# Cyusb3014_-_2.net
KiCad netlist of a schematic drawn in Altium Designer
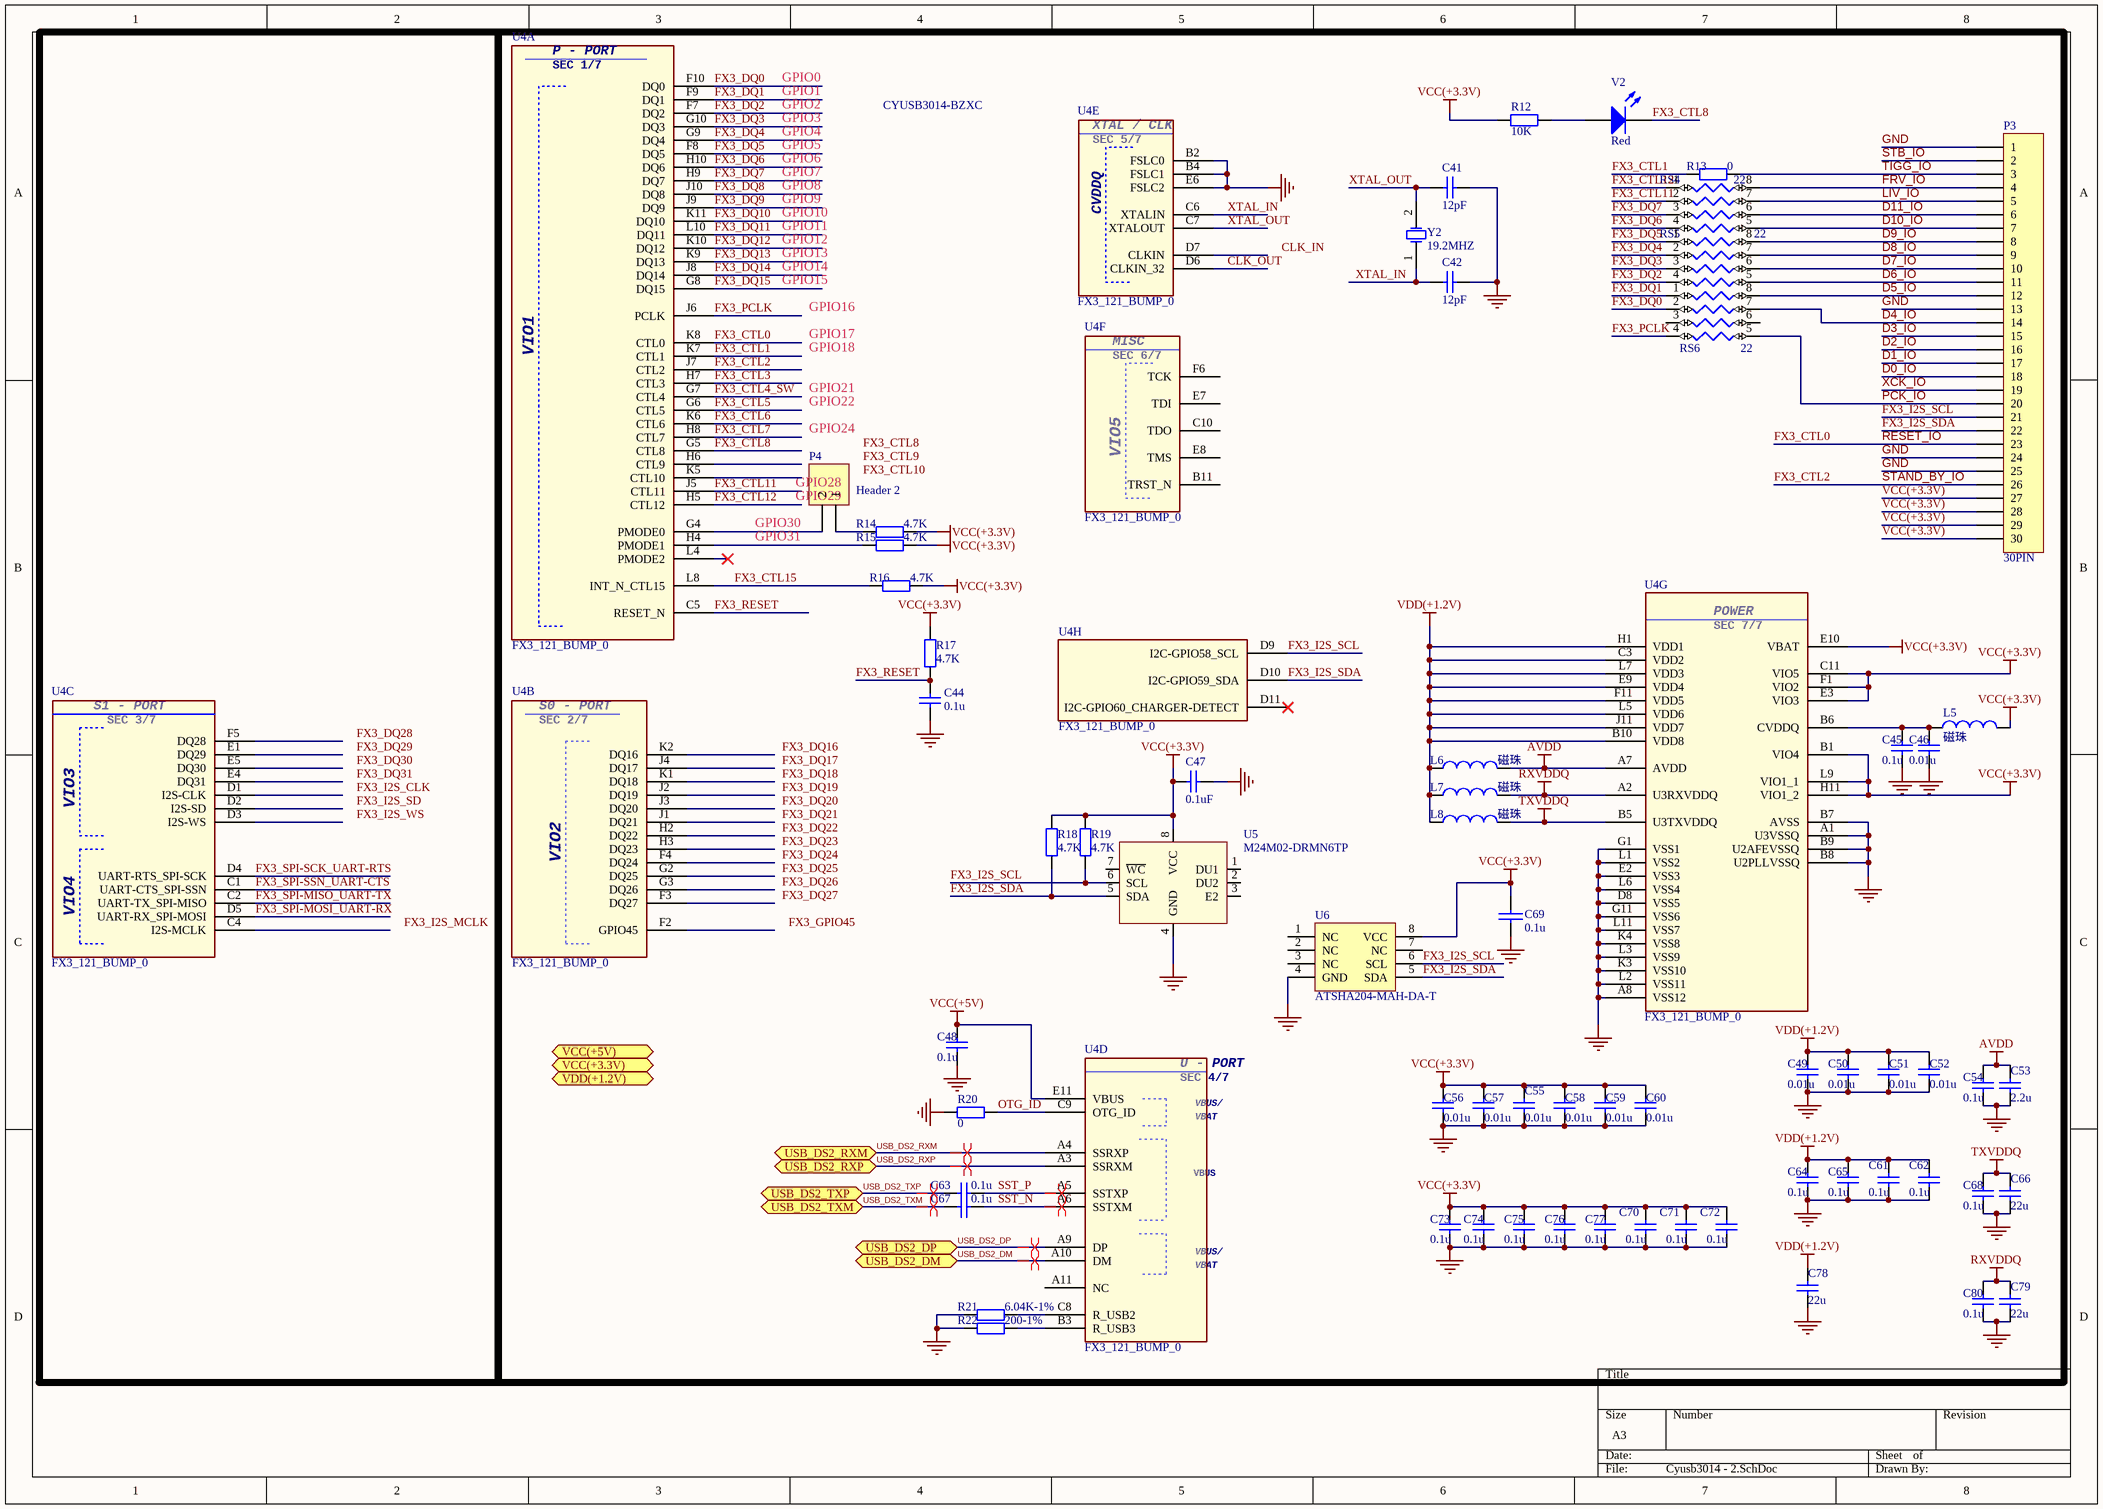
[diagram p0: Cyusb3014 - 2.SchDoc]

(export (version "E")
  (design (tool "Eeschema 10.0.6"))
  (components
    (comp (ref "C41")
      (value "12pF")
      (footprint "0603S-CAP")
      (description "CAP CER SMT 4.3pF 0805")
      (fields
        (field (name "2. MANUFACTURERE PART NUMBER") "C0805C439D5GACTU")
        (field (name "8. ALTERNATE PART") "any")
      )
      (libsource (lib "Peeple_eval") (part "CAP CER SMT 4.3pF 0805"))
    )
    (comp (ref "C42")
      (value "12pF")
      (footprint "0603S-CAP")
      (description "CAP CER SMT 4.3pF 0805")
      (fields
        (field (name "2. MANUFACTURERE PART NUMBER") "C0805C439D5GACTU")
        (field (name "8. ALTERNATE PART") "any")
      )
      (libsource (lib "Peeple_eval") (part "CAP CER SMT 4.3pF 0805"))
    )
    (comp (ref "C44")
      (value "0.1u")
      (footprint "0603S-CAP")
      (description "50V/8.2u/0805")
      (fields (field (name "PUBLISHER") "Altium Limited"))
      (libsource (lib "Miscellaneous Devices") (part "Cap"))
    )
    (comp (ref "C45")
      (value "0.1u")
      (footprint "C0402")
      (description "Capacitor")
      (fields (field (name "PUBLISHER") "Altium Limited"))
      (libsource (lib "WM360") (part "CAP0805"))
    )
    (comp (ref "C46")
      (value "0.01u")
      (footprint "C0402")
      (description "Capacitor")
      (fields (field (name "PUBLISHER") "Altium Limited"))
      (libsource (lib "WM360") (part "CAP0805"))
    )
    (comp (ref "C47")
      (value "0.1uF")
      (footprint "0603S-CAP")
      (description "CAP SMT 0.1uF 16V X7R")
      (fields
        (field (name "2. MANUFACTURERE PART NUMBER") "C0805C104K4RACTU")
        (field (name "8. ALTERNATE PART") "any")
      )
      (libsource (lib "Peeple_eval") (part "CAP SMT 0.1uF 16V X7R"))
    )
    (comp (ref "C48")
      (value "0.1u")
      (footprint "C0402")
      (description "Capacitor")
      (fields (field (name "PUBLISHER") "Altium Limited"))
      (libsource (lib "WM360") (part "CAP0805"))
    )
    (comp (ref "C49")
      (value "0.01u")
      (footprint "C0402")
      (description "Capacitor")
      (fields (field (name "PUBLISHER") "Altium Limited"))
      (libsource (lib "WM360") (part "CAP0805"))
    )
    (comp (ref "C50")
      (value "0.01u")
      (footprint "C0402")
      (description "Capacitor")
      (fields (field (name "PUBLISHER") "Altium Limited"))
      (libsource (lib "WM360") (part "CAP0805"))
    )
    (comp (ref "C51")
      (value "0.01u")
      (footprint "C0402")
      (description "Capacitor")
      (fields (field (name "PUBLISHER") "Altium Limited"))
      (libsource (lib "WM360") (part "CAP0805"))
    )
    (comp (ref "C52")
      (value "0.01u")
      (footprint "C0402")
      (description "Capacitor")
      (fields (field (name "PUBLISHER") "Altium Limited"))
      (libsource (lib "WM360") (part "CAP0805"))
    )
    (comp (ref "C53")
      (value "2.2u")
      (footprint "C0805S-CAP")
      (description "Capacitor")
      (fields (field (name "PUBLISHER") "Altium Limited"))
      (libsource (lib "USB_CAMERA") (part "CAP0805"))
    )
    (comp (ref "C54")
      (value "0.1u")
      (footprint "C0402")
      (description "Capacitor")
      (fields (field (name "PUBLISHER") "Altium Limited"))
      (libsource (lib "WM360") (part "CAP0805"))
    )
    (comp (ref "C55")
      (value "0.01u")
      (footprint "C0402")
      (description "Capacitor")
      (fields (field (name "PUBLISHER") "Altium Limited"))
      (libsource (lib "WM360") (part "CAP0805"))
    )
    (comp (ref "C56")
      (value "0.01u")
      (footprint "C0402")
      (description "Capacitor")
      (fields (field (name "PUBLISHER") "Altium Limited"))
      (libsource (lib "WM360") (part "CAP0805"))
    )
    (comp (ref "C57")
      (value "0.01u")
      (footprint "C0402")
      (description "Capacitor")
      (fields (field (name "PUBLISHER") "Altium Limited"))
      (libsource (lib "WM360") (part "CAP0805"))
    )
    (comp (ref "C58")
      (value "0.01u")
      (footprint "C0402")
      (description "Capacitor")
      (fields (field (name "PUBLISHER") "Altium Limited"))
      (libsource (lib "WM360") (part "CAP0805"))
    )
    (comp (ref "C59")
      (value "0.01u")
      (footprint "C0402")
      (description "Capacitor")
      (fields (field (name "PUBLISHER") "Altium Limited"))
      (libsource (lib "WM360") (part "CAP0805"))
    )
    (comp (ref "C60")
      (value "0.01u")
      (footprint "C0402")
      (description "Capacitor")
      (fields (field (name "PUBLISHER") "Altium Limited"))
      (libsource (lib "WM360") (part "CAP0805"))
    )
    (comp (ref "C61")
      (value "0.1u")
      (footprint "C0402")
      (description "Capacitor")
      (fields (field (name "PUBLISHER") "Altium Limited"))
      (libsource (lib "WM360") (part "CAP0805"))
    )
    (comp (ref "C62")
      (value "0.1u")
      (footprint "C0402")
      (description "Capacitor")
      (fields (field (name "PUBLISHER") "Altium Limited"))
      (libsource (lib "WM360") (part "CAP0805"))
    )
    (comp (ref "C63")
      (value "0.1u")
      (footprint "C0402")
      (description "Capacitor")
      (fields (field (name "PUBLISHER") "Altium Limited"))
      (libsource (lib "WM360") (part "CAP0805"))
    )
    (comp (ref "C64")
      (value "0.1u")
      (footprint "C0402")
      (description "Capacitor")
      (fields (field (name "PUBLISHER") "Altium Limited"))
      (libsource (lib "WM360") (part "CAP0805"))
    )
    (comp (ref "C65")
      (value "0.1u")
      (footprint "C0402")
      (description "Capacitor")
      (fields (field (name "PUBLISHER") "Altium Limited"))
      (libsource (lib "WM360") (part "CAP0805"))
    )
    (comp (ref "C66")
      (value "22u")
      (footprint "C0805S-CAP")
      (description "Capacitor")
      (fields (field (name "PUBLISHER") "Altium Limited"))
      (libsource (lib "USB_CAMERA") (part "CAP0805"))
    )
    (comp (ref "C67")
      (value "0.1u")
      (footprint "C0402")
      (description "Capacitor")
      (fields (field (name "PUBLISHER") "Altium Limited"))
      (libsource (lib "WM360") (part "CAP0805"))
    )
    (comp (ref "C68")
      (value "0.1u")
      (footprint "C0402")
      (description "Capacitor")
      (fields (field (name "PUBLISHER") "Altium Limited"))
      (libsource (lib "WM360") (part "CAP0805"))
    )
    (comp (ref "C69")
      (value "0.1u")
      (footprint "0603S-CAP")
      (description "RC=1206")
      (libsource (lib "*") (part "CAP"))
    )
    (comp (ref "C70")
      (value "0.1u")
      (footprint "C0402")
      (description "Capacitor")
      (fields (field (name "PUBLISHER") "Altium Limited"))
      (libsource (lib "WM360") (part "CAP0805"))
    )
    (comp (ref "C71")
      (value "0.1u")
      (footprint "C0402")
      (description "Capacitor")
      (fields (field (name "PUBLISHER") "Altium Limited"))
      (libsource (lib "WM360") (part "CAP0805"))
    )
    (comp (ref "C72")
      (value "0.1u")
      (footprint "C0402")
      (description "Capacitor")
      (fields (field (name "PUBLISHER") "Altium Limited"))
      (libsource (lib "WM360") (part "CAP0805"))
    )
    (comp (ref "C73")
      (value "0.1u")
      (footprint "C0402")
      (description "Capacitor")
      (fields (field (name "PUBLISHER") "Altium Limited"))
      (libsource (lib "WM360") (part "CAP0805"))
    )
    (comp (ref "C74")
      (value "0.1u")
      (footprint "C0402")
      (description "Capacitor")
      (fields (field (name "PUBLISHER") "Altium Limited"))
      (libsource (lib "WM360") (part "CAP0805"))
    )
    (comp (ref "C75")
      (value "0.1u")
      (footprint "C0402")
      (description "Capacitor")
      (fields (field (name "PUBLISHER") "Altium Limited"))
      (libsource (lib "WM360") (part "CAP0805"))
    )
    (comp (ref "C76")
      (value "0.1u")
      (footprint "C0402")
      (description "Capacitor")
      (fields (field (name "PUBLISHER") "Altium Limited"))
      (libsource (lib "WM360") (part "CAP0805"))
    )
    (comp (ref "C77")
      (value "0.1u")
      (footprint "C0402")
      (description "Capacitor")
      (fields (field (name "PUBLISHER") "Altium Limited"))
      (libsource (lib "WM360") (part "CAP0805"))
    )
    (comp (ref "C78")
      (value "22u")
      (footprint "C0805S-CAP")
      (description "Capacitor")
      (fields (field (name "PUBLISHER") "Altium Limited"))
      (libsource (lib "USB_CAMERA") (part "CAP0805"))
    )
    (comp (ref "C79")
      (value "22u")
      (footprint "C0805S-CAP")
      (description "Capacitor")
      (fields (field (name "PUBLISHER") "Altium Limited"))
      (libsource (lib "USB_CAMERA") (part "CAP0805"))
    )
    (comp (ref "C80")
      (value "0.1u")
      (footprint "C0402")
      (description "Capacitor")
      (fields (field (name "PUBLISHER") "Altium Limited"))
      (libsource (lib "WM360") (part "CAP0805"))
    )
    (comp (ref "L5")
      (value "磁珠")
      (footprint "L0603")
      (description "Inductor")
      (fields (field (name "PUBLISHER") "Altium Limited"))
      (libsource (lib "Miscellaneous Devices") (part "Inductor"))
    )
    (comp (ref "L6")
      (value "磁珠")
      (footprint "L0603")
      (description "Inductor")
      (fields (field (name "PUBLISHER") "Altium Limited"))
      (libsource (lib "Miscellaneous Devices") (part "Inductor"))
    )
    (comp (ref "L7")
      (value "磁珠")
      (footprint "L0603")
      (description "Inductor")
      (fields (field (name "PUBLISHER") "Altium Limited"))
      (libsource (lib "Miscellaneous Devices") (part "Inductor"))
    )
    (comp (ref "L8")
      (value "磁珠")
      (footprint "L0603")
      (description "Inductor")
      (fields (field (name "PUBLISHER") "Altium Limited"))
      (libsource (lib "Miscellaneous Devices") (part "Inductor"))
    )
    (comp (ref "P3")
      (value "30PIN")
      (footprint "FH12-30S-0.5SH")
      (description "Header, 30-Pin")
      (fields (field (name "PUBLISHER") "Altium Limited"))
      (libsource (lib "Miscellaneous Connectors") (part "Header 30"))
    )
    (comp (ref "P4")
      (value "Header 2")
      (footprint "HDR1X2")
      (description "Header, 2-Pin")
      (fields (field (name "PUBLISHER") "Altium Limited"))
      (libsource (lib "Miscellaneous Connectors") (part "Header 2"))
    )
    (comp (ref "R12")
      (value "10K")
      (footprint "0603S-RES")
      (description "Resistor")
      (fields (field (name "PUBLISHER") "Altium Limited"))
      (libsource (lib "DM642") (part "Res2"))
    )
    (comp (ref "R13")
      (value "0")
      (footprint "0603S-RES")
      (description "Resistor")
      (fields (field (name "PUBLISHER") "Altium Limited"))
      (libsource (lib "DM642") (part "Res2"))
    )
    (comp (ref "R14")
      (value "4.7K")
      (footprint "0603S-RES")
      (description "Resistor")
      (fields (field (name "PUBLISHER") "Altium Limited"))
      (libsource (lib "") (part "Res2_3"))
    )
    (comp (ref "R15")
      (value "4.7K")
      (footprint "0603S-RES")
      (description "Resistor")
      (fields (field (name "PUBLISHER") "Altium Limited"))
      (libsource (lib "") (part "Res2_3"))
    )
    (comp (ref "R16")
      (value "4.7K")
      (footprint "0603S-RES")
      (description "Resistor")
      (fields (field (name "PUBLISHER") "Altium Limited"))
      (libsource (lib "") (part "Res2_1"))
    )
    (comp (ref "R17")
      (value "4.7K")
      (footprint "0603S-RES")
      (description "Resistor")
      (fields (field (name "PUBLISHER") "Altium Limited"))
      (libsource (lib "") (part "Res2_2"))
    )
    (comp (ref "R18")
      (value "4.7K")
      (footprint "0603S-RES")
      (description "Resistor")
      (fields (field (name "PUBLISHER") "Altium Limited"))
      (libsource (lib "") (part "Res2_3"))
    )
    (comp (ref "R19")
      (value "4.7K")
      (footprint "0603S-RES")
      (description "Resistor")
      (fields (field (name "PUBLISHER") "Altium Limited"))
      (libsource (lib "") (part "Res2_3"))
    )
    (comp (ref "R20")
      (value "0")
      (footprint "0603S-RES")
      (description "Resistor")
      (fields (field (name "PUBLISHER") "Altium Limited"))
      (libsource (lib "") (part "Res2_1"))
    )
    (comp (ref "R21")
      (value "6.04K-1%")
      (footprint "0603S-RES")
      (description "Resistor")
      (fields (field (name "PUBLISHER") "Altium Limited"))
      (libsource (lib "") (part "Res2_1"))
    )
    (comp (ref "R22")
      (value "200-1%")
      (footprint "0603S-RES")
      (description "Resistor")
      (fields (field (name "PUBLISHER") "Altium Limited"))
      (libsource (lib "") (part "Res2_1"))
    )
    (comp (ref "RS4") (value "22") (footprint "NC06-4") (libsource (lib "*") (part "RN4")))
    (comp (ref "RS5") (value "22") (footprint "NC06-4") (libsource (lib "*") (part "RN4")))
    (comp (ref "RS6") (value "22") (footprint "NC06-4") (libsource (lib "*") (part "RN4")))
    (comp (ref "U4")
      (value "FX3_121_BUMP_0")
      (footprint "121_BGA_FX3")
      (libsource (lib "") (part "FX3_121_BUMP_0_1"))
    )
    (comp (ref "U5")
      (value "M24M02-DRMN6TP")
      (footprint "SOIC127P600X175-8N")
      (description "IC EEPROM 64KBIT 400KHZ 8SOIC")
      (fields
        (field (name "MANUFACTURER") "Microchip Technology")
        (field (name "MANUFACTURER PART NUMBER") "24LC64-I/SN")
      )
      (libsource (lib "Schlib1") (part "24LC64-I/SN"))
    )
    (comp (ref "U6")
      (value "ATSHA204-MAH-DA-T")
      (footprint "UDFN")
      (libsource (lib "CY7C68013-56") (part "AT24C128"))
    )
    (comp (ref "V2")
      (value "Red")
      (footprint "LED0805S")
      (description "Typical INFRARED GaAs LED")
      (fields (field (name "PUBLISHER") "Altium Limited"))
      (libsource (lib "DM642") (part "LED0"))
    )
    (comp (ref "Y2")
      (value "19.2MHZ")
      (footprint "爱普生晶振3.2×2.5MM - 无源")
      (description "Crystal, CRYSTAL 32.768KHZ 6PF SMD")
      (fields
        (field (name "2. MANUFACTURERE PART NUMBER") "ABS07-120-32.768KHZ-T")
        (field (name "4. SUPPLIER PART NUMBER") "535-11937-1-ND")
      )
      (libsource (lib "Peeple_eval") (part "XTAL 32.768KHZ"))
    )
  )
  (nets
    (net (code "2") (name "/CLK_OUT") (class "Default")
      (node (ref "U4") (pin "D6") (pinfunction "CLKIN_32_D6") (pintype "passive"))
    )
    (net (code "3") (name "/D0_IO") (class "Default")
      (node (ref "P3") (pin "18") (pinfunction "18_18") (pintype "passive"))
    )
    (net (code "4") (name "/D1_IO") (class "Default")
      (node (ref "P3") (pin "17") (pinfunction "17_17") (pintype "passive"))
    )
    (net (code "5") (name "/D2_IO") (class "Default")
      (node (ref "P3") (pin "16") (pinfunction "16_16") (pintype "passive"))
    )
    (net (code "6") (name "/D3_IO") (class "Default")
      (node (ref "P3") (pin "15") (pinfunction "15_15") (pintype "passive"))
    )
    (net (code "7") (name "/D4_IO") (class "Default")
      (node (ref "P3") (pin "14") (pinfunction "14_14") (pintype "passive"))
      (node (ref "RS6") (pin "7") (pinfunction "7_7") (pintype "bidirectional"))
    )
    (net (code "8") (name "/D5_IO") (class "Default")
      (node (ref "P3") (pin "12") (pinfunction "12_12") (pintype "passive"))
      (node (ref "RS6") (pin "8") (pinfunction "8_8") (pintype "bidirectional"))
    )
    (net (code "9") (name "/D6_IO") (class "Default")
      (node (ref "P3") (pin "11") (pinfunction "11_11") (pintype "passive"))
      (node (ref "RS5") (pin "5") (pinfunction "5_5") (pintype "bidirectional"))
    )
    (net (code "10") (name "/D7_IO") (class "Default")
      (node (ref "P3") (pin "10") (pinfunction "10_10") (pintype "passive"))
      (node (ref "RS5") (pin "6") (pinfunction "6_6") (pintype "bidirectional"))
    )
    (net (code "11") (name "/D8_IO") (class "Default")
      (node (ref "P3") (pin "9") (pinfunction "9_9") (pintype "passive"))
      (node (ref "RS5") (pin "7") (pinfunction "7_7") (pintype "bidirectional"))
    )
    (net (code "12") (name "/D9_IO") (class "Default")
      (node (ref "P3") (pin "8") (pinfunction "8_8") (pintype "passive"))
      (node (ref "RS5") (pin "8") (pinfunction "8_8") (pintype "bidirectional"))
    )
    (net (code "13") (name "/D10_IO") (class "Default")
      (node (ref "P3") (pin "7") (pinfunction "7_7") (pintype "passive"))
      (node (ref "RS4") (pin "5") (pinfunction "5_5") (pintype "bidirectional"))
    )
    (net (code "14") (name "/D11_IO") (class "Default")
      (node (ref "P3") (pin "6") (pinfunction "6_6") (pintype "passive"))
      (node (ref "RS4") (pin "6") (pinfunction "6_6") (pintype "bidirectional"))
    )
    (net (code "15") (name "/FRV_IO") (class "Default")
      (node (ref "P3") (pin "4") (pinfunction "4_4") (pintype "passive"))
      (node (ref "RS4") (pin "8") (pinfunction "8_8") (pintype "bidirectional"))
    )
    (net (code "16") (name "/FX3_CTL0") (class "Default")
      (node (ref "P3") (pin "23") (pinfunction "23_23") (pintype "passive"))
      (node (ref "U4") (pin "K8") (pinfunction "CTL0_K8") (pintype "passive"))
    )
    (net (code "17") (name "/FX3_CTL1") (class "Default")
      (node (ref "R13") (pin "2") (pinfunction "2_2") (pintype "passive"))
      (node (ref "U4") (pin "K7") (pinfunction "CTL1_K7") (pintype "passive"))
    )
    (net (code "18") (name "/FX3_CTL2") (class "Default")
      (node (ref "P3") (pin "26") (pinfunction "26_26") (pintype "passive"))
      (node (ref "U4") (pin "J7") (pinfunction "CTL2_J7") (pintype "passive"))
    )
    (net (code "19") (name "/FX3_CTL3") (class "Default")
      (node (ref "U4") (pin "H7") (pinfunction "CTL3_H7") (pintype "passive"))
    )
    (net (code "20") (name "/FX3_CTL4_SW") (class "Default")
      (node (ref "U4") (pin "G7") (pinfunction "CTL4_G7") (pintype "passive"))
    )
    (net (code "21") (name "/FX3_CTL5") (class "Default")
      (node (ref "U4") (pin "G6") (pinfunction "CTL5_G6") (pintype "passive"))
    )
    (net (code "22") (name "/FX3_CTL6") (class "Default")
      (node (ref "U4") (pin "K6") (pinfunction "CTL6_K6") (pintype "passive"))
    )
    (net (code "23") (name "/FX3_CTL7") (class "Default")
      (node (ref "U4") (pin "H8") (pinfunction "CTL7_H8") (pintype "passive"))
    )
    (net (code "24") (name "/FX3_CTL8") (class "Default")
      (node (ref "U4") (pin "G5") (pinfunction "CTL8_G5") (pintype "passive"))
      (node (ref "V2") (pin "2") (pinfunction "K_2") (pintype "passive"))
    )
    (net (code "27") (name "/FX3_CTL11") (class "Default")
      (node (ref "RS4") (pin "2") (pinfunction "2_2") (pintype "bidirectional"))
      (node (ref "U4") (pin "J5") (pinfunction "CTL11_J5") (pintype "passive"))
    )
    (net (code "28") (name "/FX3_CTL12") (class "Default")
      (node (ref "RS4") (pin "1") (pinfunction "1_1") (pintype "bidirectional"))
      (node (ref "U4") (pin "H5") (pinfunction "CTL12_H5") (pintype "passive"))
    )
    (net (code "29") (name "/FX3_CTL15") (class "Default")
      (node (ref "R16") (pin "2") (pinfunction "2_2") (pintype "passive"))
      (node (ref "U4") (pin "L8") (pinfunction "INT_N_CTL15_L8") (pintype "passive"))
    )
    (net (code "30") (name "/FX3_DQ0") (class "Default")
      (node (ref "RS6") (pin "2") (pinfunction "2_2") (pintype "bidirectional"))
      (node (ref "U4") (pin "F10") (pinfunction "DQ0_F10") (pintype "passive"))
    )
    (net (code "31") (name "/FX3_DQ1") (class "Default")
      (node (ref "RS6") (pin "1") (pinfunction "1_1") (pintype "bidirectional"))
      (node (ref "U4") (pin "F9") (pinfunction "DQ1_F9") (pintype "passive"))
    )
    (net (code "32") (name "/FX3_DQ2") (class "Default")
      (node (ref "RS5") (pin "4") (pinfunction "4_4") (pintype "bidirectional"))
      (node (ref "U4") (pin "F7") (pinfunction "DQ2_F7") (pintype "passive"))
    )
    (net (code "33") (name "/FX3_DQ3") (class "Default")
      (node (ref "RS5") (pin "3") (pinfunction "3_3") (pintype "bidirectional"))
      (node (ref "U4") (pin "G10") (pinfunction "DQ3_G10") (pintype "passive"))
    )
    (net (code "34") (name "/FX3_DQ4") (class "Default")
      (node (ref "RS5") (pin "2") (pinfunction "2_2") (pintype "bidirectional"))
      (node (ref "U4") (pin "G9") (pinfunction "DQ4_G9") (pintype "passive"))
    )
    (net (code "35") (name "/FX3_DQ5") (class "Default")
      (node (ref "RS5") (pin "1") (pinfunction "1_1") (pintype "bidirectional"))
      (node (ref "U4") (pin "F8") (pinfunction "DQ5_F8") (pintype "passive"))
    )
    (net (code "36") (name "/FX3_DQ6") (class "Default")
      (node (ref "RS4") (pin "4") (pinfunction "4_4") (pintype "bidirectional"))
      (node (ref "U4") (pin "H10") (pinfunction "DQ6_H10") (pintype "passive"))
    )
    (net (code "37") (name "/FX3_DQ7") (class "Default")
      (node (ref "RS4") (pin "3") (pinfunction "3_3") (pintype "bidirectional"))
      (node (ref "U4") (pin "H9") (pinfunction "DQ7_H9") (pintype "passive"))
    )
    (net (code "38") (name "/FX3_DQ8") (class "Default")
      (node (ref "U4") (pin "J10") (pinfunction "DQ8_J10") (pintype "passive"))
    )
    (net (code "39") (name "/FX3_DQ9") (class "Default")
      (node (ref "U4") (pin "J9") (pinfunction "DQ9_J9") (pintype "passive"))
    )
    (net (code "40") (name "/FX3_DQ10") (class "Default")
      (node (ref "U4") (pin "K11") (pinfunction "DQ10_K11") (pintype "passive"))
    )
    (net (code "41") (name "/FX3_DQ11") (class "Default")
      (node (ref "U4") (pin "L10") (pinfunction "DQ11_L10") (pintype "passive"))
    )
    (net (code "42") (name "/FX3_DQ12") (class "Default")
      (node (ref "U4") (pin "K10") (pinfunction "DQ12_K10") (pintype "passive"))
    )
    (net (code "43") (name "/FX3_DQ13") (class "Default")
      (node (ref "U4") (pin "K9") (pinfunction "DQ13_K9") (pintype "passive"))
    )
    (net (code "44") (name "/FX3_DQ14") (class "Default")
      (node (ref "U4") (pin "J8") (pinfunction "DQ14_J8") (pintype "passive"))
    )
    (net (code "45") (name "/FX3_DQ15") (class "Default")
      (node (ref "U4") (pin "G8") (pinfunction "DQ15_G8") (pintype "passive"))
    )
    (net (code "65") (name "/FX3_I2S_SCL") (class "Default")
      (node (ref "P3") (pin "21") (pinfunction "21_21") (pintype "passive"))
      (node (ref "R19") (pin "1") (pinfunction "1_1") (pintype "passive"))
      (node (ref "U4") (pin "D9") (pinfunction "I2C-GPIO58_SCL_D9") (pintype "passive"))
      (node (ref "U5") (pin "6") (pinfunction "SCL_6") (pintype "passive"))
      (node (ref "U6") (pin "6") (pinfunction "SCL_6") (pintype "passive"))
    )
    (net (code "67") (name "/FX3_I2S_SDA") (class "Default")
      (node (ref "P3") (pin "22") (pinfunction "22_22") (pintype "passive"))
      (node (ref "R18") (pin "1") (pinfunction "1_1") (pintype "passive"))
      (node (ref "U4") (pin "D10") (pinfunction "I2C-GPIO59_SDA_D10") (pintype "passive"))
      (node (ref "U5") (pin "5") (pinfunction "SDA_5") (pintype "passive"))
      (node (ref "U6") (pin "5") (pinfunction "SDA_5") (pintype "passive"))
    )
    (net (code "69") (name "/FX3_PCLK") (class "Default")
      (node (ref "RS6") (pin "4") (pinfunction "4_4") (pintype "bidirectional"))
      (node (ref "U4") (pin "J6") (pinfunction "PCLK_J6") (pintype "passive"))
    )
    (net (code "70") (name "/FX3_RESET") (class "Default")
      (node (ref "C44") (pin "2") (pinfunction "2_2") (pintype "passive"))
      (node (ref "R17") (pin "2") (pinfunction "2_2") (pintype "passive"))
      (node (ref "U4") (pin "C5") (pinfunction "RESET_N_C5") (pintype "passive"))
    )
    (net (code "71") (name "/FX3_SPI-MISO_UART-TX") (class "Default")
      (node (ref "U4") (pin "C2") (pinfunction "UART-TX_SPI-MISO_C2") (pintype "passive"))
    )
    (net (code "72") (name "/FX3_SPI-MOSI_UART-RX") (class "Default")
      (node (ref "U4") (pin "D5") (pinfunction "UART-RX_SPI-MOSI_D5") (pintype "passive"))
    )
    (net (code "73") (name "/FX3_SPI-SCK_UART-RTS") (class "Default")
      (node (ref "U4") (pin "D4") (pinfunction "UART-RTS_SPI-SCK_D4") (pintype "passive"))
    )
    (net (code "74") (name "/FX3_SPI-SSN_UART-CTS") (class "Default")
      (node (ref "U4") (pin "C1") (pinfunction "UART-CTS_SPI-SSN_C1") (pintype "passive"))
    )
    (net (code "75") (name "/LIV_IO") (class "Default")
      (node (ref "P3") (pin "5") (pinfunction "5_5") (pintype "passive"))
      (node (ref "RS4") (pin "7") (pinfunction "7_7") (pintype "bidirectional"))
    )
    (net (code "76") (name "/OTG_ID") (class "Default")
      (node (ref "R20") (pin "1") (pinfunction "1_1") (pintype "passive"))
      (node (ref "U4") (pin "C9") (pinfunction "OTG_ID_C9") (pintype "passive"))
    )
    (net (code "77") (name "/PCK_IO") (class "Default")
      (node (ref "P3") (pin "20") (pinfunction "20_20") (pintype "passive"))
      (node (ref "RS6") (pin "5") (pinfunction "5_5") (pintype "bidirectional"))
    )
    (net (code "78") (name "/SST_N") (class "Default")
      (node (ref "C67") (pin "2") (pinfunction "2_2") (pintype "passive"))
      (node (ref "U4") (pin "A6") (pinfunction "SSTXM_A6") (pintype "passive"))
    )
    (net (code "79") (name "/SST_P") (class "Default")
      (node (ref "C63") (pin "2") (pinfunction "2_2") (pintype "passive"))
      (node (ref "U4") (pin "A5") (pinfunction "SSTXP_A5") (pintype "passive"))
    )
    (net (code "80") (name "/STB_IO") (class "Default")
      (node (ref "P3") (pin "2") (pinfunction "2_2") (pintype "passive"))
    )
    (net (code "81") (name "/TIGG_IO") (class "Default")
      (node (ref "P3") (pin "3") (pinfunction "3_3") (pintype "passive"))
      (node (ref "R13") (pin "1") (pinfunction "1_1") (pintype "passive"))
    )
    (net (code "82") (name "/USB_DS2_DM") (class "Default")
      (node (ref "U4") (pin "A10") (pinfunction "DM_A10") (pintype "passive"))
    )
    (net (code "83") (name "/USB_DS2_DP") (class "Default")
      (node (ref "U4") (pin "A9") (pinfunction "DP_A9") (pintype "passive"))
    )
    (net (code "84") (name "/USB_DS2_RXM") (class "Default")
      (node (ref "U4") (pin "A4") (pinfunction "SSRXP_A4") (pintype "passive"))
    )
    (net (code "85") (name "/USB_DS2_RXP") (class "Default")
      (node (ref "U4") (pin "A3") (pinfunction "SSRXM_A3") (pintype "passive"))
    )
    (net (code "86") (name "/USB_DS2_TXM") (class "Default")
      (node (ref "C67") (pin "1") (pinfunction "1_1") (pintype "passive"))
    )
    (net (code "87") (name "/USB_DS2_TXP") (class "Default")
      (node (ref "C63") (pin "1") (pinfunction "1_1") (pintype "passive"))
    )
    (net (code "88") (name "/XCK_IO") (class "Default")
      (node (ref "P3") (pin "19") (pinfunction "19_19") (pintype "passive"))
    )
    (net (code "89") (name "/XTAL_IN") (class "Default")
      (node (ref "C42") (pin "2") (pinfunction "2_2") (pintype "passive"))
      (node (ref "U4") (pin "C6") (pinfunction "XTALIN_C6") (pintype "passive"))
      (node (ref "Y2") (pin "1") (pinfunction "OSC1_1") (pintype "passive"))
    )
    (net (code "90") (name "/XTAL_OUT") (class "Default")
      (node (ref "C41") (pin "2") (pinfunction "2_2") (pintype "passive"))
      (node (ref "U4") (pin "C7") (pinfunction "XTALOUT_C7") (pintype "passive"))
      (node (ref "Y2") (pin "2") (pinfunction "OSC2_2") (pintype "passive"))
    )
    (net (code "91") (name "AVDD") (class "Default")
      (node (ref "C53") (pin "2") (pinfunction "2_2") (pintype "passive"))
      (node (ref "C54") (pin "1") (pinfunction "1_1") (pintype "passive"))
      (node (ref "L6") (pin "2") (pinfunction "2_2") (pintype "passive"))
      (node (ref "U4") (pin "A7") (pinfunction "AVDD_A7") (pintype "passive"))
    )
    (net (code "92") (name "GND") (class "Default")
      (node (ref "C41") (pin "1") (pinfunction "1_1") (pintype "passive"))
      (node (ref "C42") (pin "1") (pinfunction "1_1") (pintype "passive"))
      (node (ref "C44") (pin "1") (pinfunction "1_1") (pintype "passive"))
      (node (ref "C45") (pin "2") (pinfunction "2_2") (pintype "passive"))
      (node (ref "C46") (pin "2") (pinfunction "2_2") (pintype "passive"))
      (node (ref "C47") (pin "1") (pinfunction "1_1") (pintype "passive"))
      (node (ref "C48") (pin "2") (pinfunction "2_2") (pintype "passive"))
      (node (ref "C49") (pin "2") (pinfunction "2_2") (pintype "passive"))
      (node (ref "C50") (pin "2") (pinfunction "2_2") (pintype "passive"))
      (node (ref "C51") (pin "2") (pinfunction "2_2") (pintype "passive"))
      (node (ref "C52") (pin "2") (pinfunction "2_2") (pintype "passive"))
      (node (ref "C53") (pin "1") (pinfunction "1_1") (pintype "passive"))
      (node (ref "C54") (pin "2") (pinfunction "2_2") (pintype "passive"))
      (node (ref "C55") (pin "2") (pinfunction "2_2") (pintype "passive"))
      (node (ref "C56") (pin "2") (pinfunction "2_2") (pintype "passive"))
      (node (ref "C57") (pin "2") (pinfunction "2_2") (pintype "passive"))
      (node (ref "C58") (pin "2") (pinfunction "2_2") (pintype "passive"))
      (node (ref "C59") (pin "2") (pinfunction "2_2") (pintype "passive"))
      (node (ref "C60") (pin "2") (pinfunction "2_2") (pintype "passive"))
      (node (ref "C61") (pin "2") (pinfunction "2_2") (pintype "passive"))
      (node (ref "C62") (pin "2") (pinfunction "2_2") (pintype "passive"))
      (node (ref "C64") (pin "2") (pinfunction "2_2") (pintype "passive"))
      (node (ref "C65") (pin "2") (pinfunction "2_2") (pintype "passive"))
      (node (ref "C66") (pin "1") (pinfunction "1_1") (pintype "passive"))
      (node (ref "C68") (pin "2") (pinfunction "2_2") (pintype "passive"))
      (node (ref "C69") (pin "2") (pintype "passive"))
      (node (ref "C70") (pin "2") (pinfunction "2_2") (pintype "passive"))
      (node (ref "C71") (pin "2") (pinfunction "2_2") (pintype "passive"))
      (node (ref "C72") (pin "2") (pinfunction "2_2") (pintype "passive"))
      (node (ref "C73") (pin "2") (pinfunction "2_2") (pintype "passive"))
      (node (ref "C74") (pin "2") (pinfunction "2_2") (pintype "passive"))
      (node (ref "C75") (pin "2") (pinfunction "2_2") (pintype "passive"))
      (node (ref "C76") (pin "2") (pinfunction "2_2") (pintype "passive"))
      (node (ref "C77") (pin "2") (pinfunction "2_2") (pintype "passive"))
      (node (ref "C78") (pin "1") (pinfunction "1_1") (pintype "passive"))
      (node (ref "C79") (pin "1") (pinfunction "1_1") (pintype "passive"))
      (node (ref "C80") (pin "2") (pinfunction "2_2") (pintype "passive"))
      (node (ref "P3") (pin "1") (pinfunction "1_1") (pintype "passive"))
      (node (ref "P3") (pin "13") (pinfunction "13_13") (pintype "passive"))
      (node (ref "P3") (pin "24") (pinfunction "24_24") (pintype "passive"))
      (node (ref "P3") (pin "25") (pinfunction "25_25") (pintype "passive"))
      (node (ref "R20") (pin "2") (pinfunction "2_2") (pintype "passive"))
      (node (ref "R21") (pin "2") (pinfunction "2_2") (pintype "passive"))
      (node (ref "R22") (pin "2") (pinfunction "2_2") (pintype "passive"))
      (node (ref "U4") (pin "A1") (pinfunction "U3VSSQ_A1") (pintype "passive"))
      (node (ref "U4") (pin "A8") (pinfunction "VSS12_A8") (pintype "passive"))
      (node (ref "U4") (pin "B2") (pinfunction "FSLC0_B2") (pintype "passive"))
      (node (ref "U4") (pin "B4") (pinfunction "FSLC1_B4") (pintype "passive"))
      (node (ref "U4") (pin "B7") (pinfunction "AVSS_B7") (pintype "passive"))
      (node (ref "U4") (pin "B8") (pinfunction "U2PLLVSSQ_B8") (pintype "passive"))
      (node (ref "U4") (pin "B9") (pinfunction "U2AFEVSSQ_B9") (pintype "passive"))
      (node (ref "U4") (pin "D8") (pinfunction "VSS5_D8") (pintype "passive"))
      (node (ref "U4") (pin "E2") (pinfunction "VSS3_E2") (pintype "passive"))
      (node (ref "U4") (pin "E6") (pinfunction "FSLC2_E6") (pintype "passive"))
      (node (ref "U4") (pin "G1") (pinfunction "VSS1_G1") (pintype "passive"))
      (node (ref "U4") (pin "G11") (pinfunction "VSS6_G11") (pintype "passive"))
      (node (ref "U4") (pin "K3") (pinfunction "VSS10_K3") (pintype "passive"))
      (node (ref "U4") (pin "K4") (pinfunction "VSS8_K4") (pintype "passive"))
      (node (ref "U4") (pin "L1") (pinfunction "VSS2_L1") (pintype "passive"))
      (node (ref "U4") (pin "L11") (pinfunction "VSS7_L11") (pintype "passive"))
      (node (ref "U4") (pin "L2") (pinfunction "VSS11_L2") (pintype "passive"))
      (node (ref "U4") (pin "L3") (pinfunction "VSS9_L3") (pintype "passive"))
      (node (ref "U4") (pin "L6") (pinfunction "VSS4_L6") (pintype "passive"))
      (node (ref "U5") (pin "4") (pinfunction "GND_4") (pintype "passive"))
      (node (ref "U6") (pin "4") (pinfunction "GND_4") (pintype "passive"))
    )
    (net (code "93") (name "Net-(P4-Pad1)") (class "Default")
      (node (ref "P4") (pin "1") (pinfunction "1_1") (pintype "passive"))
      (node (ref "R14") (pin "1") (pinfunction "1_1") (pintype "passive"))
    )
    (net (code "94") (name "Net-(U4A-PMODE0)") (class "Default")
      (node (ref "P4") (pin "2") (pinfunction "2_2") (pintype "passive"))
      (node (ref "U4") (pin "G4") (pinfunction "PMODE0_G4") (pintype "passive"))
    )
    (net (code "95") (name "Net-(U4A-PMODE1)") (class "Default")
      (node (ref "R15") (pin "1") (pinfunction "1_1") (pintype "passive"))
      (node (ref "U4") (pin "H4") (pinfunction "PMODE1_H4") (pintype "passive"))
    )
    (net (code "96") (name "Net-(U4D-R_USB2)") (class "Default")
      (node (ref "R21") (pin "1") (pinfunction "1_1") (pintype "passive"))
      (node (ref "U4") (pin "C8") (pinfunction "R_USB2_C8") (pintype "passive"))
    )
    (net (code "97") (name "Net-(U4D-R_USB3)") (class "Default")
      (node (ref "R22") (pin "1") (pinfunction "1_1") (pintype "passive"))
      (node (ref "U4") (pin "B3") (pinfunction "R_USB3_B3") (pintype "passive"))
    )
    (net (code "98") (name "Net-(U4G-CVDDQ)") (class "Default")
      (node (ref "C45") (pin "1") (pinfunction "1_1") (pintype "passive"))
      (node (ref "C46") (pin "1") (pinfunction "1_1") (pintype "passive"))
      (node (ref "L5") (pin "1") (pinfunction "1_1") (pintype "passive"))
      (node (ref "U4") (pin "B6") (pinfunction "CVDDQ_B6") (pintype "passive"))
    )
    (net (code "99") (name "Net-(V2-A)") (class "Default")
      (node (ref "R12") (pin "1") (pinfunction "1_1") (pintype "passive"))
      (node (ref "V2") (pin "1") (pinfunction "A_1") (pintype "passive"))
    )
    (net (code "100") (name "RXVDDQ") (class "Default")
      (node (ref "C79") (pin "2") (pinfunction "2_2") (pintype "passive"))
      (node (ref "C80") (pin "1") (pinfunction "1_1") (pintype "passive"))
      (node (ref "L7") (pin "2") (pinfunction "2_2") (pintype "passive"))
      (node (ref "U4") (pin "A2") (pinfunction "U3RXVDDQ_A2") (pintype "passive"))
    )
    (net (code "101") (name "TXVDDQ") (class "Default")
      (node (ref "C66") (pin "2") (pinfunction "2_2") (pintype "passive"))
      (node (ref "C68") (pin "1") (pinfunction "1_1") (pintype "passive"))
      (node (ref "L8") (pin "2") (pinfunction "2_2") (pintype "passive"))
      (node (ref "U4") (pin "B5") (pinfunction "U3TXVDDQ_B5") (pintype "passive"))
    )
    (net (code "102") (name "VCC(+3.3V)") (class "Default")
      (node (ref "C47") (pin "2") (pinfunction "2_2") (pintype "passive"))
      (node (ref "C55") (pin "1") (pinfunction "1_1") (pintype "passive"))
      (node (ref "C56") (pin "1") (pinfunction "1_1") (pintype "passive"))
      (node (ref "C57") (pin "1") (pinfunction "1_1") (pintype "passive"))
      (node (ref "C58") (pin "1") (pinfunction "1_1") (pintype "passive"))
      (node (ref "C59") (pin "1") (pinfunction "1_1") (pintype "passive"))
      (node (ref "C60") (pin "1") (pinfunction "1_1") (pintype "passive"))
      (node (ref "C69") (pin "1") (pintype "passive"))
      (node (ref "C70") (pin "1") (pinfunction "1_1") (pintype "passive"))
      (node (ref "C71") (pin "1") (pinfunction "1_1") (pintype "passive"))
      (node (ref "C72") (pin "1") (pinfunction "1_1") (pintype "passive"))
      (node (ref "C73") (pin "1") (pinfunction "1_1") (pintype "passive"))
      (node (ref "C74") (pin "1") (pinfunction "1_1") (pintype "passive"))
      (node (ref "C75") (pin "1") (pinfunction "1_1") (pintype "passive"))
      (node (ref "C76") (pin "1") (pinfunction "1_1") (pintype "passive"))
      (node (ref "C77") (pin "1") (pinfunction "1_1") (pintype "passive"))
      (node (ref "L5") (pin "2") (pinfunction "2_2") (pintype "passive"))
      (node (ref "P3") (pin "27") (pinfunction "27_27") (pintype "passive"))
      (node (ref "P3") (pin "28") (pinfunction "28_28") (pintype "passive"))
      (node (ref "P3") (pin "29") (pinfunction "29_29") (pintype "passive"))
      (node (ref "P3") (pin "30") (pinfunction "30_30") (pintype "passive"))
      (node (ref "R12") (pin "2") (pinfunction "2_2") (pintype "passive"))
      (node (ref "R14") (pin "2") (pinfunction "2_2") (pintype "passive"))
      (node (ref "R15") (pin "2") (pinfunction "2_2") (pintype "passive"))
      (node (ref "R16") (pin "1") (pinfunction "1_1") (pintype "passive"))
      (node (ref "R17") (pin "1") (pinfunction "1_1") (pintype "passive"))
      (node (ref "R18") (pin "2") (pinfunction "2_2") (pintype "passive"))
      (node (ref "R19") (pin "2") (pinfunction "2_2") (pintype "passive"))
      (node (ref "U4") (pin "B1") (pinfunction "VIO4_B1") (pintype "passive"))
      (node (ref "U4") (pin "C11") (pinfunction "VIO5_C11") (pintype "passive"))
      (node (ref "U4") (pin "E10") (pinfunction "VBAT_E10") (pintype "passive"))
      (node (ref "U4") (pin "E3") (pinfunction "VIO3_E3") (pintype "passive"))
      (node (ref "U4") (pin "F1") (pinfunction "VIO2_F1") (pintype "passive"))
      (node (ref "U4") (pin "H11") (pinfunction "VIO1_2_H11") (pintype "passive"))
      (node (ref "U4") (pin "L9") (pinfunction "VIO1_1_L9") (pintype "passive"))
      (node (ref "U5") (pin "8") (pinfunction "VCC_8") (pintype "passive"))
      (node (ref "U6") (pin "8") (pinfunction "VCC_8") (pintype "passive"))
    )
    (net (code "103") (name "VCC(+5V)") (class "Default")
      (node (ref "C48") (pin "1") (pinfunction "1_1") (pintype "passive"))
      (node (ref "U4") (pin "E11") (pinfunction "VBUS_E11") (pintype "passive"))
    )
    (net (code "104") (name "VDD(+1.2V)") (class "Default")
      (node (ref "C49") (pin "1") (pinfunction "1_1") (pintype "passive"))
      (node (ref "C50") (pin "1") (pinfunction "1_1") (pintype "passive"))
      (node (ref "C51") (pin "1") (pinfunction "1_1") (pintype "passive"))
      (node (ref "C52") (pin "1") (pinfunction "1_1") (pintype "passive"))
      (node (ref "C61") (pin "1") (pinfunction "1_1") (pintype "passive"))
      (node (ref "C62") (pin "1") (pinfunction "1_1") (pintype "passive"))
      (node (ref "C64") (pin "1") (pinfunction "1_1") (pintype "passive"))
      (node (ref "C65") (pin "1") (pinfunction "1_1") (pintype "passive"))
      (node (ref "C78") (pin "2") (pinfunction "2_2") (pintype "passive"))
      (node (ref "L6") (pin "1") (pinfunction "1_1") (pintype "passive"))
      (node (ref "L7") (pin "1") (pinfunction "1_1") (pintype "passive"))
      (node (ref "L8") (pin "1") (pinfunction "1_1") (pintype "passive"))
      (node (ref "U4") (pin "B10") (pinfunction "VDD8_B10") (pintype "passive"))
      (node (ref "U4") (pin "C3") (pinfunction "VDD2_C3") (pintype "passive"))
      (node (ref "U4") (pin "E9") (pinfunction "VDD4_E9") (pintype "passive"))
      (node (ref "U4") (pin "F11") (pinfunction "VDD5_F11") (pintype "passive"))
      (node (ref "U4") (pin "H1") (pinfunction "VDD1_H1") (pintype "passive"))
      (node (ref "U4") (pin "J11") (pinfunction "VDD7_J11") (pintype "passive"))
      (node (ref "U4") (pin "L5") (pinfunction "VDD6_L5") (pintype "passive"))
      (node (ref "U4") (pin "L7") (pinfunction "VDD3_L7") (pintype "passive"))
    )
    (net (code "105") (name "unconnected-(RS6-Pad3)") (class "Default")
      (node (ref "RS6") (pin "3") (pinfunction "3_3") (pintype "bidirectional"))
    )
    (net (code "106") (name "unconnected-(RS6-Pad6)") (class "Default")
      (node (ref "RS6") (pin "6") (pinfunction "6_6") (pintype "bidirectional"))
    )
    (net (code "107") (name "unconnected-(U4A-CTL9-PadH6)") (class "Default")
      (node (ref "U4") (pin "H6") (pinfunction "CTL9_H6") (pintype "passive"))
    )
    (net (code "108") (name "unconnected-(U4A-CTL10-PadK5)") (class "Default")
      (node (ref "U4") (pin "K5") (pinfunction "CTL10_K5") (pintype "passive"))
    )
    (net (code "109") (name "unconnected-(U4A-PMODE2-PadL4)") (class "Default")
      (node (ref "U4") (pin "L4") (pinfunction "PMODE2_L4") (pintype "passive+no_connect"))
    )
    (net (code "110") (name "unconnected-(U4B-DQ16-PadK2)") (class "Default")
      (node (ref "U4") (pin "K2") (pinfunction "DQ16_K2") (pintype "passive"))
    )
    (net (code "111") (name "unconnected-(U4B-DQ17-PadJ4)") (class "Default")
      (node (ref "U4") (pin "J4") (pinfunction "DQ17_J4") (pintype "passive"))
    )
    (net (code "112") (name "unconnected-(U4B-DQ18-PadK1)") (class "Default")
      (node (ref "U4") (pin "K1") (pinfunction "DQ18_K1") (pintype "passive"))
    )
    (net (code "113") (name "unconnected-(U4B-DQ19-PadJ2)") (class "Default")
      (node (ref "U4") (pin "J2") (pinfunction "DQ19_J2") (pintype "passive"))
    )
    (net (code "114") (name "unconnected-(U4B-DQ20-PadJ3)") (class "Default")
      (node (ref "U4") (pin "J3") (pinfunction "DQ20_J3") (pintype "passive"))
    )
    (net (code "115") (name "unconnected-(U4B-DQ21-PadJ1)") (class "Default")
      (node (ref "U4") (pin "J1") (pinfunction "DQ21_J1") (pintype "passive"))
    )
    (net (code "116") (name "unconnected-(U4B-DQ22-PadH2)") (class "Default")
      (node (ref "U4") (pin "H2") (pinfunction "DQ22_H2") (pintype "passive"))
    )
    (net (code "117") (name "unconnected-(U4B-DQ23-PadH3)") (class "Default")
      (node (ref "U4") (pin "H3") (pinfunction "DQ23_H3") (pintype "passive"))
    )
    (net (code "118") (name "unconnected-(U4B-DQ24-PadF4)") (class "Default")
      (node (ref "U4") (pin "F4") (pinfunction "DQ24_F4") (pintype "passive"))
    )
    (net (code "119") (name "unconnected-(U4B-DQ25-PadG2)") (class "Default")
      (node (ref "U4") (pin "G2") (pinfunction "DQ25_G2") (pintype "passive"))
    )
    (net (code "120") (name "unconnected-(U4B-DQ26-PadG3)") (class "Default")
      (node (ref "U4") (pin "G3") (pinfunction "DQ26_G3") (pintype "passive"))
    )
    (net (code "121") (name "unconnected-(U4B-DQ27-PadF3)") (class "Default")
      (node (ref "U4") (pin "F3") (pinfunction "DQ27_F3") (pintype "passive"))
    )
    (net (code "122") (name "unconnected-(U4B-GPIO45-PadF2)") (class "Default")
      (node (ref "U4") (pin "F2") (pinfunction "GPIO45_F2") (pintype "passive"))
    )
    (net (code "123") (name "unconnected-(U4C-DQ28-PadF5)") (class "Default")
      (node (ref "U4") (pin "F5") (pinfunction "DQ28_F5") (pintype "passive"))
    )
    (net (code "124") (name "unconnected-(U4C-DQ29-PadE1)") (class "Default")
      (node (ref "U4") (pin "E1") (pinfunction "DQ29_E1") (pintype "passive"))
    )
    (net (code "125") (name "unconnected-(U4C-DQ30-PadE5)") (class "Default")
      (node (ref "U4") (pin "E5") (pinfunction "DQ30_E5") (pintype "passive"))
    )
    (net (code "126") (name "unconnected-(U4C-DQ31-PadE4)") (class "Default")
      (node (ref "U4") (pin "E4") (pinfunction "DQ31_E4") (pintype "passive"))
    )
    (net (code "127") (name "unconnected-(U4C-I2S-CLK-PadD1)") (class "Default")
      (node (ref "U4") (pin "D1") (pinfunction "I2S-CLK_D1") (pintype "passive"))
    )
    (net (code "128") (name "unconnected-(U4C-I2S-MCLK-PadC4)") (class "Default")
      (node (ref "U4") (pin "C4") (pinfunction "I2S-MCLK_C4") (pintype "passive"))
    )
    (net (code "129") (name "unconnected-(U4C-I2S-SD-PadD2)") (class "Default")
      (node (ref "U4") (pin "D2") (pinfunction "I2S-SD_D2") (pintype "passive"))
    )
    (net (code "130") (name "unconnected-(U4C-I2S-WS-PadD3)") (class "Default")
      (node (ref "U4") (pin "D3") (pinfunction "I2S-WS_D3") (pintype "passive"))
    )
    (net (code "131") (name "unconnected-(U4D-NC-PadA11)") (class "Default")
      (node (ref "U4") (pin "A11") (pinfunction "NC_A11") (pintype "passive"))
    )
    (net (code "132") (name "unconnected-(U4E-CLKIN-PadD7)") (class "Default")
      (node (ref "U4") (pin "D7") (pinfunction "CLKIN_D7") (pintype "passive"))
    )
    (net (code "133") (name "unconnected-(U4F-TCK-PadF6)") (class "Default")
      (node (ref "U4") (pin "F6") (pinfunction "TCK_F6") (pintype "passive"))
    )
    (net (code "134") (name "unconnected-(U4F-TDI-PadE7)") (class "Default")
      (node (ref "U4") (pin "E7") (pinfunction "TDI_E7") (pintype "passive"))
    )
    (net (code "135") (name "unconnected-(U4F-TDO-PadC10)") (class "Default")
      (node (ref "U4") (pin "C10") (pinfunction "TDO_C10") (pintype "passive"))
    )
    (net (code "136") (name "unconnected-(U4F-TMS-PadE8)") (class "Default")
      (node (ref "U4") (pin "E8") (pinfunction "TMS_E8") (pintype "passive"))
    )
    (net (code "137") (name "unconnected-(U4F-TRST_N-PadB11)") (class "Default")
      (node (ref "U4") (pin "B11") (pinfunction "TRST_N_B11") (pintype "passive"))
    )
    (net (code "138") (name "unconnected-(U4H-I2C-GPIO60_CHARGER-DETECT-PadD11)") (class "Default")
      (node (ref "U4") (pin "D11") (pinfunction "I2C-GPIO60_CHARGER-DETECT_D11") (pintype "passive+no_connect"))
    )
    (net (code "139") (name "unconnected-(U5-DU1-Pad1)") (class "Default")
      (node (ref "U5") (pin "1") (pinfunction "DU1_1") (pintype "passive"))
    )
    (net (code "140") (name "unconnected-(U5-DU2-Pad2)") (class "Default")
      (node (ref "U5") (pin "2") (pinfunction "DU2_2") (pintype "passive"))
    )
    (net (code "141") (name "unconnected-(U5-E2-Pad3)") (class "Default")
      (node (ref "U5") (pin "3") (pinfunction "E2_3") (pintype "passive"))
    )
    (net (code "142") (name "unconnected-(U5-~{WC}-Pad7)") (class "Default")
      (node (ref "U5") (pin "7") (pinfunction "~{WC}_7") (pintype "passive"))
    )
    (net (code "143") (name "unconnected-(U6-NC-Pad1)") (class "Default")
      (node (ref "U6") (pin "1") (pinfunction "NC_1") (pintype "passive"))
    )
    (net (code "144") (name "unconnected-(U6-NC-Pad2)") (class "Default")
      (node (ref "U6") (pin "2") (pinfunction "NC_2") (pintype "passive"))
    )
    (net (code "145") (name "unconnected-(U6-NC-Pad3)") (class "Default")
      (node (ref "U6") (pin "3") (pinfunction "NC_3") (pintype "passive"))
    )
    (net (code "146") (name "unconnected-(U6-NC-Pad7)") (class "Default")
      (node (ref "U6") (pin "7") (pinfunction "NC_7") (pintype "passive"))
    )
  )
)
